# schematic_complete.net
KiCad netlist of a schematic drawn in Altium Designer
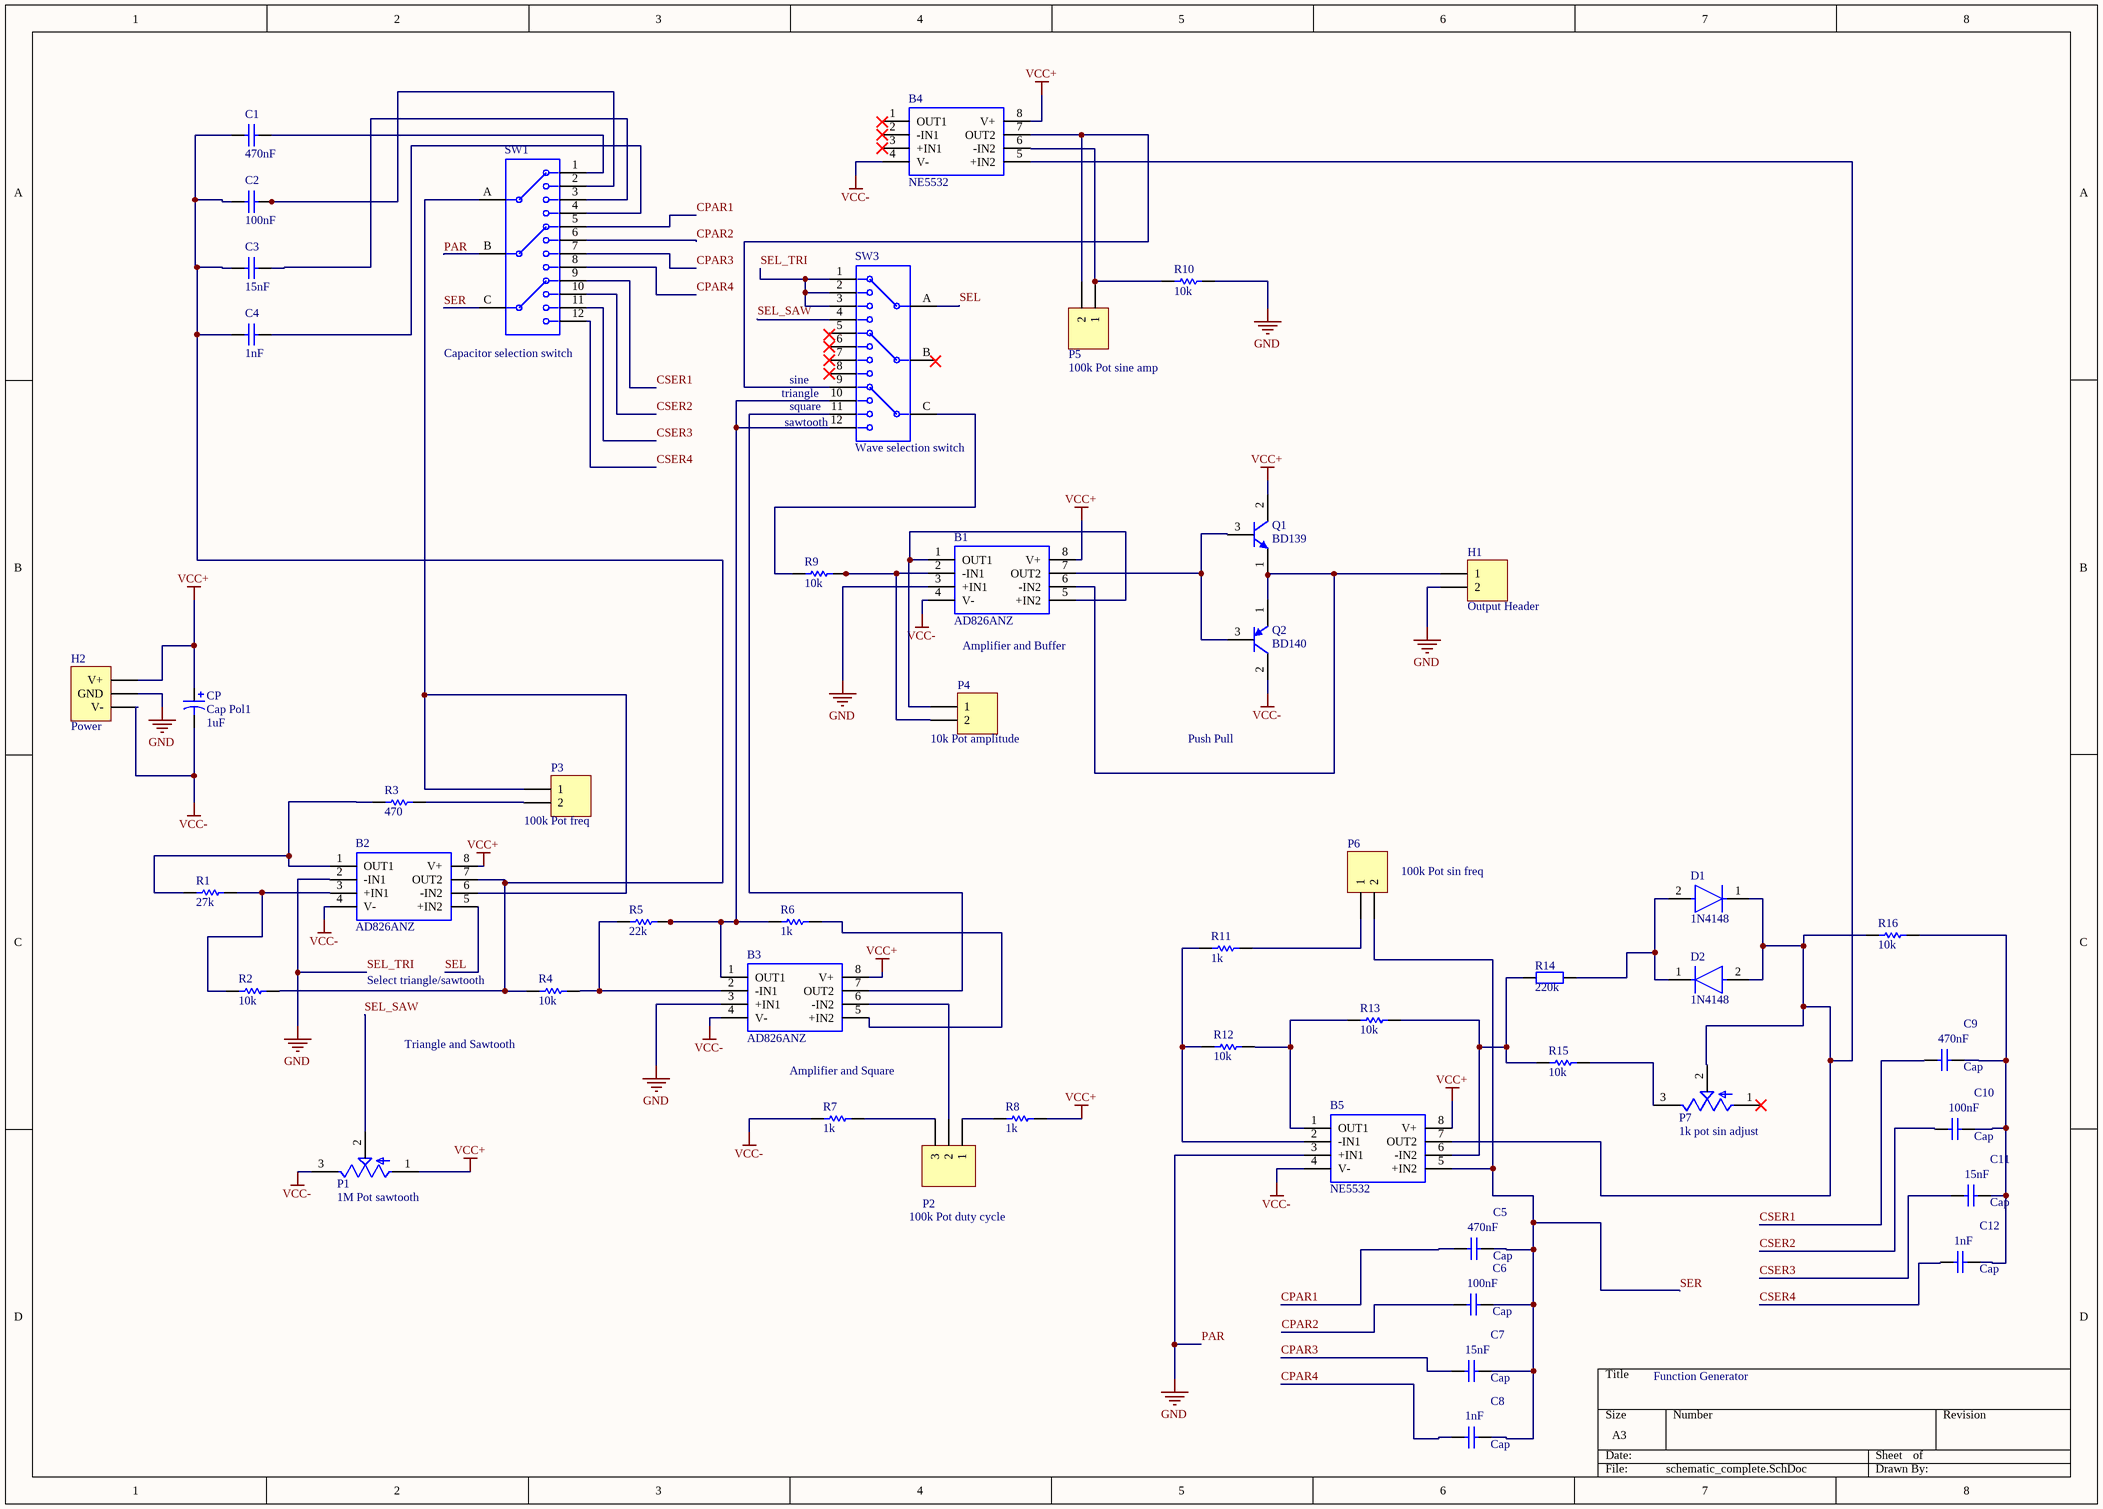
[diagram p0: schematic_complete.SchDoc]

(export (version "E")
  (design (tool "Eeschema 10.0.6"))
  (components
    (comp (ref "B1")
      (value "AD826ANZ")
      (footprint "DIP794W56P254L959H533Q8N")
      (description "AD826ANZ, Dual Operational Amplifier Voltage Feedback 29MHz 9 to 28V, 8-Pin MPDIP")
      (fields (field (name "MOUSER PART NUMBER") "584-AD826ANZ"))
      (libsource (lib "AD826ANZ") (part "AD826ANZ"))
    )
    (comp (ref "B2")
      (value "AD826ANZ")
      (footprint "DIP794W56P254L959H533Q8N")
      (description "AD826ANZ, Dual Operational Amplifier Voltage Feedback 29MHz 9 to 28V, 8-Pin MPDIP")
      (fields (field (name "MOUSER PART NUMBER") "584-AD826ANZ"))
      (libsource (lib "AD826ANZ") (part "AD826ANZ"))
    )
    (comp (ref "B3")
      (value "AD826ANZ")
      (footprint "DIP794W56P254L959H533Q8N:DIP794W56P254L959H533Q8N")
      (description "AD826ANZ, Dual Operational Amplifier Voltage Feedback 29MHz 9 to 28V, 8-Pin MPDIP")
      (fields (field (name "MOUSER PART NUMBER") "584-AD826ANZ"))
      (libsource (lib "AD826ANZ") (part "AD826ANZ"))
    )
    (comp (ref "B4")
      (value "NE5532")
      (footprint "DIP794W56P254L959H533Q8N")
      (description "AD826ANZ, Dual Operational Amplifier Voltage Feedback 29MHz 9 to 28V, 8-Pin MPDIP")
      (fields
        (field (name "MANUFACTURER_PART_NUMBER") "AD826ANZ")
        (field (name "MOUSER PART NUMBER") "584-AD826ANZ")
      )
      (libsource (lib "AD826ANZ") (part "AD826ANZ"))
    )
    (comp (ref "B5")
      (value "NE5532")
      (footprint "DIP794W56P254L959H533Q8N")
      (description "AD826ANZ, Dual Operational Amplifier Voltage Feedback 29MHz 9 to 28V, 8-Pin MPDIP")
      (fields
        (field (name "MANUFACTURER_PART_NUMBER") "AD826ANZ")
        (field (name "MOUSER PART NUMBER") "584-AD826ANZ")
      )
      (libsource (lib "switch") (part "AD826ANZ"))
    )
    (comp (ref "C1")
      (value "470nF")
      (footprint "RAD-0.3")
      (description "Capacitor")
      (fields (field (name "PUBLISHER") "Altium Limited"))
      (libsource (lib "Miscellaneous Devices") (part "Cap"))
    )
    (comp (ref "C2")
      (value "100nF")
      (footprint "RAD-0.3")
      (description "Capacitor")
      (fields (field (name "PUBLISHER") "Altium Limited"))
      (libsource (lib "Miscellaneous Devices") (part "Cap"))
    )
    (comp (ref "C3")
      (value "15nF")
      (footprint "RAD-0.3")
      (description "Capacitor")
      (fields (field (name "PUBLISHER") "Altium Limited"))
      (libsource (lib "Miscellaneous Devices") (part "Cap"))
    )
    (comp (ref "C4")
      (value "1nF")
      (footprint "RAD-0.3")
      (description "Capacitor")
      (fields (field (name "PUBLISHER") "Altium Limited"))
      (libsource (lib "Miscellaneous Devices") (part "Cap"))
    )
    (comp (ref "C5")
      (value "Cap")
      (footprint "RAD-0.3")
      (description "Capacitor")
      (fields (field (name "ALTIUM_VALUE") "470nF") (field (name "PUBLISHER") "Altium Limited"))
      (libsource (lib "Miscellaneous Devices") (part "Cap"))
    )
    (comp (ref "C6")
      (value "Cap")
      (footprint "RAD-0.3")
      (description "Capacitor")
      (fields (field (name "ALTIUM_VALUE") "100nF") (field (name "PUBLISHER") "Altium Limited"))
      (libsource (lib "Miscellaneous Devices") (part "Cap"))
    )
    (comp (ref "C7")
      (value "Cap")
      (footprint "RAD-0.3")
      (description "Capacitor")
      (fields (field (name "ALTIUM_VALUE") "15nF") (field (name "PUBLISHER") "Altium Limited"))
      (libsource (lib "Miscellaneous Devices") (part "Cap"))
    )
    (comp (ref "C8")
      (value "Cap")
      (footprint "RAD-0.3")
      (description "Capacitor")
      (fields (field (name "ALTIUM_VALUE") "1nF") (field (name "PUBLISHER") "Altium Limited"))
      (libsource (lib "Miscellaneous Devices") (part "Cap"))
    )
    (comp (ref "C9")
      (value "Cap")
      (footprint "RAD-0.3")
      (description "Capacitor")
      (fields (field (name "ALTIUM_VALUE") "470nF") (field (name "PUBLISHER") "Altium Limited"))
      (libsource (lib "Miscellaneous Devices") (part "Cap"))
    )
    (comp (ref "C10")
      (value "Cap")
      (footprint "RAD-0.3")
      (description "Capacitor")
      (fields (field (name "ALTIUM_VALUE") "100nF") (field (name "PUBLISHER") "Altium Limited"))
      (libsource (lib "Miscellaneous Devices") (part "Cap"))
    )
    (comp (ref "C11")
      (value "Cap")
      (footprint "RAD-0.3")
      (description "Capacitor")
      (fields (field (name "ALTIUM_VALUE") "15nF") (field (name "PUBLISHER") "Altium Limited"))
      (libsource (lib "Miscellaneous Devices") (part "Cap"))
    )
    (comp (ref "C12")
      (value "Cap")
      (footprint "RAD-0.3")
      (description "Capacitor")
      (fields (field (name "ALTIUM_VALUE") "1nF") (field (name "PUBLISHER") "Altium Limited"))
      (libsource (lib "Miscellaneous Devices") (part "Cap"))
    )
    (comp (ref "CP")
      (value "Cap Pol1")
      (footprint "RB7.6-15")
      (description "Polarized Capacitor (Radial)")
      (fields (field (name "ALTIUM_VALUE") "1uF") (field (name "PUBLISHER") "Altium Limited"))
      (libsource (lib "Miscellaneous Devices") (part "Cap Pol1"))
    )
    (comp (ref "D1")
      (value "1N4148")
      (footprint "FP-017AG-MFG")
      (description "DIODE GEN PURP 100V 200MA DO35")
      (fields (field (name "VOLTAGE") "100V"))
      (libsource (lib "Altium Content Vault") (part "d7152d700b627762746794eb795d46e"))
    )
    (comp (ref "D2")
      (value "1N4148")
      (footprint "FP-017AG-MFG")
      (description "DIODE GEN PURP 100V 200MA DO35")
      (fields (field (name "VOLTAGE") "100V"))
      (libsource (lib "Altium Content Vault") (part "d7152d700b627762746794eb795d46e"))
    )
    (comp (ref "H1")
      (value "Output Header")
      (footprint "HDR1X2")
      (description "Header, 2-Pin")
      (fields (field (name "PUBLISHER") "Altium Limited"))
      (libsource (lib "Miscellaneous Connectors") (part "Header 2"))
    )
    (comp (ref "H2")
      (value "Power")
      (footprint "HDR1X3")
      (description "Header, 3-Pin")
      (fields (field (name "PUBLISHER") "Altium Limited"))
      (libsource (lib "Miscellaneous Connectors") (part "Header 3"))
    )
    (comp (ref "P1")
      (value "1M Pot sawtooth")
      (footprint "TRIM_3362P-1-253LF")
      (description "25 kOhms 0.5W, 1/2W PC Pins Through Hole Trimmer Potentiometer Cermet 1 Turn Top Adjustment")
      (fields (field (name "MF") "Bourns") (field (name "MP") "3362P-1-253LF"))
      (libsource (lib "3362P-1-253LF") (part "3362P-1-253LF"))
    )
    (comp (ref "P2")
      (value "100k Pot duty cycle")
      (footprint "HDR1X3")
      (description "Header, 3-Pin")
      (fields (field (name "PUBLISHER") "Altium Limited"))
      (libsource (lib "Miscellaneous Connectors") (part "Header 3"))
    )
    (comp (ref "P3")
      (value "100k Pot freq")
      (footprint "HDR1X2")
      (description "Header, 2-Pin")
      (fields (field (name "PUBLISHER") "Altium Limited"))
      (libsource (lib "Miscellaneous Connectors") (part "Header 2"))
    )
    (comp (ref "P4")
      (value "10k Pot amplitude")
      (footprint "HDR1X2")
      (description "Header, 2-Pin")
      (fields (field (name "PUBLISHER") "Altium Limited"))
      (libsource (lib "Miscellaneous Connectors") (part "Header 2"))
    )
    (comp (ref "P5")
      (value "100k Pot sine amp")
      (footprint "HDR1X2")
      (description "Header, 2-Pin")
      (fields (field (name "PUBLISHER") "Altium Limited"))
      (libsource (lib "") (part "Header 2_2"))
    )
    (comp (ref "P6")
      (value "100k Pot sin freq")
      (footprint "HDR1X2")
      (description "Header, 2-Pin")
      (fields (field (name "PUBLISHER") "Altium Limited"))
      (libsource (lib "") (part "Header 2_1"))
    )
    (comp (ref "P7")
      (value "1k pot sin adjust")
      (footprint "TRIM_3362P-1-253LF")
      (description "25 kOhms 0.5W, 1/2W PC Pins Through Hole Trimmer Potentiometer Cermet 1 Turn Top Adjustment")
      (fields (field (name "MF") "Bourns") (field (name "MP") "3362P-1-253LF"))
      (libsource (lib "3362P-1-253LF") (part "3362P-1-253LF"))
    )
    (comp (ref "Q1")
      (value "BD139")
      (footprint "ONSC-TO-225-3-77-09")
      (description "Plastic Medium-Power Silicon NPN Transistor, 3-Pin TO-225, Bulk Box")
      (fields (field (name "MANUFACTURER") "On Semiconductor"))
      (libsource (lib "Altium Content Vault") (part "ONSC-NPN-E1C2B3-3"))
    )
    (comp (ref "Q2")
      (value "BD140")
      (footprint "ONSC-TO-225-3-77-09")
      (description "Plastic Medium-Power Silicon PNP Transistor, 3-Pin TO-225, Bulk Box")
      (fields (field (name "MANUFACTURER") "On Semiconductor"))
      (libsource (lib "Altium Content Vault") (part "ONSC-PNP-E1C2B3-3"))
    )
    (comp (ref "R1")
      (value "27k")
      (footprint "AXIAL-0.3")
      (description "Resistor")
      (fields (field (name "PUBLISHER") "Altium Limited"))
      (libsource (lib "Miscellaneous Devices") (part "Res1"))
    )
    (comp (ref "R2")
      (value "10k")
      (footprint "AXIAL-0.3")
      (description "Resistor")
      (fields (field (name "PUBLISHER") "Altium Limited"))
      (libsource (lib "Miscellaneous Devices") (part "Res1"))
    )
    (comp (ref "R3")
      (value "470")
      (footprint "AXIAL-0.3")
      (description "Resistor")
      (fields (field (name "PUBLISHER") "Altium Limited"))
      (libsource (lib "Miscellaneous Devices") (part "Res1"))
    )
    (comp (ref "R4")
      (value "10k")
      (footprint "AXIAL-0.3")
      (description "Resistor")
      (fields (field (name "PUBLISHER") "Altium Limited"))
      (libsource (lib "Miscellaneous Devices") (part "Res1"))
    )
    (comp (ref "R5")
      (value "22k")
      (footprint "AXIAL-0.3")
      (description "Resistor")
      (fields (field (name "PUBLISHER") "Altium Limited"))
      (libsource (lib "Miscellaneous Devices") (part "Res1"))
    )
    (comp (ref "R6")
      (value "1k")
      (footprint "AXIAL-0.3")
      (description "Resistor")
      (fields (field (name "PUBLISHER") "Altium Limited"))
      (libsource (lib "Miscellaneous Devices") (part "Res1"))
    )
    (comp (ref "R7")
      (value "1k")
      (footprint "AXIAL-0.3")
      (description "Resistor")
      (fields (field (name "PUBLISHER") "Altium Limited"))
      (libsource (lib "Miscellaneous Devices") (part "Res1"))
    )
    (comp (ref "R8")
      (value "1k")
      (footprint "AXIAL-0.3")
      (description "Resistor")
      (fields (field (name "PUBLISHER") "Altium Limited"))
      (libsource (lib "Miscellaneous Devices") (part "Res1"))
    )
    (comp (ref "R9")
      (value "10k")
      (footprint "AXIAL-0.3")
      (description "Resistor")
      (fields (field (name "PUBLISHER") "Altium Limited"))
      (libsource (lib "Miscellaneous Devices") (part "Res1"))
    )
    (comp (ref "R10")
      (value "10k")
      (footprint "AXIAL-0.3")
      (description "Resistor")
      (fields (field (name "PUBLISHER") "Altium Limited"))
      (libsource (lib "Miscellaneous Devices") (part "Res1"))
    )
    (comp (ref "R11")
      (value "1k")
      (footprint "AXIAL-0.3")
      (description "Resistor")
      (fields (field (name "PUBLISHER") "Altium Limited"))
      (libsource (lib "Miscellaneous Devices") (part "Res1"))
    )
    (comp (ref "R12")
      (value "10k")
      (footprint "AXIAL-0.3")
      (description "Resistor")
      (fields (field (name "PUBLISHER") "Altium Limited"))
      (libsource (lib "Miscellaneous Devices") (part "Res1"))
    )
    (comp (ref "R13")
      (value "10k")
      (footprint "AXIAL-0.3")
      (description "Resistor")
      (fields (field (name "PUBLISHER") "Altium Limited"))
      (libsource (lib "Miscellaneous Devices") (part "Res1"))
    )
    (comp (ref "R14")
      (value "220k")
      (footprint "AXIAL-0.4")
      (description "Resistor")
      (fields (field (name "PUBLISHER") "Altium Limited"))
      (libsource (lib "Miscellaneous Devices") (part "Res2"))
    )
    (comp (ref "R15")
      (value "10k")
      (footprint "AXIAL-0.3")
      (description "Resistor")
      (fields (field (name "PUBLISHER") "Altium Limited"))
      (libsource (lib "Miscellaneous Devices") (part "Res1"))
    )
    (comp (ref "R16")
      (value "10k")
      (footprint "AXIAL-0.3")
      (description "Resistor")
      (fields (field (name "PUBLISHER") "Altium Limited"))
      (libsource (lib "Miscellaneous Devices") (part "Res1"))
    )
    (comp (ref "SW1")
      (value "Capacitor selection switch")
      (footprint "SW_A30403RNCQ")
      (description "Rotary Switch 4 Position 3P4T 2.5A (AC), 350mA (DC) 125VAC Panel Mount, Through Hole")
      (fields (field (name "MP") "A30403RNCQ") (field (name "MF") "C&K"))
      (libsource (lib "A30403RNCQ") (part "A30403RNCQ"))
    )
    (comp (ref "SW3")
      (value "Wave selection switch")
      (footprint "SW_A30403RNCQ")
      (description "Rotary Switch 4 Position 3P4T 2.5A (AC), 350mA (DC) 125VAC Panel Mount, Through Hole")
      (fields (field (name "MP") "A30403RNCQ") (field (name "MF") "C&K"))
      (libsource (lib "A30403RNCQ") (part "A30403RNCQ"))
    )
  )
  (nets
    (net (code "1") (name "/CPAR1") (class "Default")
      (node (ref "C5") (pin "1") (pinfunction "1_1") (pintype "passive"))
      (node (ref "SW1") (pin "5") (pinfunction "5_5") (pintype "passive"))
    )
    (net (code "2") (name "/CPAR2") (class "Default")
      (node (ref "C6") (pin "1") (pinfunction "1_1") (pintype "passive"))
      (node (ref "SW1") (pin "6") (pinfunction "6_6") (pintype "passive"))
    )
    (net (code "3") (name "/CPAR3") (class "Default")
      (node (ref "C7") (pin "1") (pinfunction "1_1") (pintype "passive"))
      (node (ref "SW1") (pin "7") (pinfunction "7_7") (pintype "passive"))
    )
    (net (code "4") (name "/CPAR4") (class "Default")
      (node (ref "C8") (pin "1") (pinfunction "1_1") (pintype "passive"))
      (node (ref "SW1") (pin "8") (pinfunction "8_8") (pintype "passive"))
    )
    (net (code "5") (name "/CSER1") (class "Default")
      (node (ref "C9") (pin "1") (pinfunction "1_1") (pintype "passive"))
      (node (ref "SW1") (pin "9") (pinfunction "9_9") (pintype "passive"))
    )
    (net (code "6") (name "/CSER2") (class "Default")
      (node (ref "C10") (pin "1") (pinfunction "1_1") (pintype "passive"))
      (node (ref "SW1") (pin "10") (pinfunction "10_10") (pintype "passive"))
    )
    (net (code "7") (name "/CSER3") (class "Default")
      (node (ref "C11") (pin "1") (pinfunction "1_1") (pintype "passive"))
      (node (ref "SW1") (pin "11") (pinfunction "11_11") (pintype "passive"))
    )
    (net (code "8") (name "/CSER4") (class "Default")
      (node (ref "C12") (pin "1") (pinfunction "1_1") (pintype "passive"))
      (node (ref "SW1") (pin "12") (pinfunction "12_12") (pintype "passive"))
    )
    (net (code "9") (name "/SEL") (class "Default")
      (node (ref "B2") (pin "5") (pinfunction "+IN2_5") (pintype "passive"))
      (node (ref "SW3") (pin "A") (pinfunction "A_A") (pintype "passive"))
    )
    (net (code "10") (name "/SEL_SAW") (class "Default")
      (node (ref "P1") (pin "2") (pinfunction "WIPER_2") (pintype "passive"))
      (node (ref "SW3") (pin "4") (pinfunction "4_4") (pintype "passive"))
    )
    (net (code "11") (name "/SER") (class "Default")
      (node (ref "B5") (pin "5") (pinfunction "+IN2_5") (pintype "passive"))
      (node (ref "C5") (pin "2") (pinfunction "2_2") (pintype "passive"))
      (node (ref "C6") (pin "2") (pinfunction "2_2") (pintype "passive"))
      (node (ref "C7") (pin "2") (pinfunction "2_2") (pintype "passive"))
      (node (ref "C8") (pin "2") (pinfunction "2_2") (pintype "passive"))
      (node (ref "P6") (pin "2") (pinfunction "2_2") (pintype "passive"))
      (node (ref "SW1") (pin "C") (pinfunction "C_C") (pintype "passive"))
    )
    (net (code "12") (name "GND") (class "Default")
      (node (ref "B1") (pin "3") (pinfunction "+IN1_3") (pintype "passive"))
      (node (ref "B2") (pin "2") (pinfunction "-IN1_2") (pintype "passive"))
      (node (ref "B3") (pin "3") (pinfunction "+IN1_3") (pintype "passive"))
      (node (ref "B5") (pin "3") (pinfunction "+IN1_3") (pintype "passive"))
      (node (ref "H1") (pin "2") (pinfunction "2_2") (pintype "passive"))
      (node (ref "H2") (pin "2") (pinfunction "GND_2") (pintype "passive"))
      (node (ref "R10") (pin "2") (pinfunction "2_2") (pintype "passive"))
      (node (ref "SW1") (pin "B") (pinfunction "B_B") (pintype "passive"))
      (node (ref "SW3") (pin "1") (pinfunction "1_1") (pintype "passive"))
      (node (ref "SW3") (pin "2") (pinfunction "2_2") (pintype "passive"))
      (node (ref "SW3") (pin "3") (pinfunction "3_3") (pintype "passive"))
    )
    (net (code "13") (name "Net-(B1-+IN2)") (class "Default")
      (node (ref "B1") (pin "1") (pinfunction "OUT1_1") (pintype "passive"))
      (node (ref "B1") (pin "5") (pinfunction "+IN2_5") (pintype "passive"))
      (node (ref "P4") (pin "1") (pinfunction "1_1") (pintype "passive"))
    )
    (net (code "14") (name "Net-(B1--IN1)") (class "Default")
      (node (ref "B1") (pin "2") (pinfunction "-IN1_2") (pintype "passive"))
      (node (ref "P4") (pin "2") (pinfunction "2_2") (pintype "passive"))
      (node (ref "R9") (pin "2") (pinfunction "2_2") (pintype "passive"))
    )
    (net (code "15") (name "Net-(B1--IN2)") (class "Default")
      (node (ref "B1") (pin "6") (pinfunction "-IN2_6") (pintype "passive"))
      (node (ref "H1") (pin "1") (pinfunction "1_1") (pintype "passive"))
      (node (ref "Q1") (pin "1") (pinfunction "E_1") (pintype "passive"))
      (node (ref "Q2") (pin "1") (pinfunction "E_1") (pintype "passive"))
    )
    (net (code "16") (name "Net-(B1-OUT2)") (class "Default")
      (node (ref "B1") (pin "7") (pinfunction "OUT2_7") (pintype "passive"))
      (node (ref "Q1") (pin "3") (pinfunction "B_3") (pintype "passive"))
      (node (ref "Q2") (pin "3") (pinfunction "B_3") (pintype "passive"))
    )
    (net (code "17") (name "Net-(B2-+IN1)") (class "Default")
      (node (ref "B2") (pin "3") (pinfunction "+IN1_3") (pintype "passive"))
      (node (ref "R1") (pin "2") (pinfunction "2_2") (pintype "passive"))
      (node (ref "R2") (pin "1") (pinfunction "1_1") (pintype "passive"))
    )
    (net (code "18") (name "Net-(B2--IN2)") (class "Default")
      (node (ref "B2") (pin "6") (pinfunction "-IN2_6") (pintype "passive"))
      (node (ref "P3") (pin "1") (pinfunction "1_1") (pintype "passive"))
      (node (ref "SW1") (pin "A") (pinfunction "A_A") (pintype "passive"))
    )
    (net (code "19") (name "Net-(B2-OUT1)") (class "Default")
      (node (ref "B2") (pin "1") (pinfunction "OUT1_1") (pintype "passive"))
      (node (ref "R1") (pin "1") (pinfunction "1_1") (pintype "passive"))
      (node (ref "R3") (pin "1") (pinfunction "1_1") (pintype "passive"))
    )
    (net (code "20") (name "Net-(B2-OUT2)") (class "Default")
      (node (ref "B2") (pin "7") (pinfunction "OUT2_7") (pintype "passive"))
      (node (ref "C1") (pin "1") (pinfunction "1_1") (pintype "passive"))
      (node (ref "C2") (pin "1") (pinfunction "1_1") (pintype "passive"))
      (node (ref "C3") (pin "1") (pinfunction "1_1") (pintype "passive"))
      (node (ref "C4") (pin "1") (pinfunction "1_1") (pintype "passive"))
      (node (ref "R2") (pin "2") (pinfunction "2_2") (pintype "passive"))
      (node (ref "R4") (pin "1") (pinfunction "1_1") (pintype "passive"))
    )
    (net (code "21") (name "Net-(B3-+IN2)") (class "Default")
      (node (ref "B3") (pin "5") (pinfunction "+IN2_5") (pintype "passive"))
      (node (ref "R6") (pin "2") (pinfunction "2_2") (pintype "passive"))
    )
    (net (code "22") (name "Net-(B3--IN1)") (class "Default")
      (node (ref "B3") (pin "2") (pinfunction "-IN1_2") (pintype "passive"))
      (node (ref "R4") (pin "2") (pinfunction "2_2") (pintype "passive"))
      (node (ref "R5") (pin "1") (pinfunction "1_1") (pintype "passive"))
    )
    (net (code "23") (name "Net-(B3--IN2)") (class "Default")
      (node (ref "B3") (pin "6") (pinfunction "-IN2_6") (pintype "passive"))
      (node (ref "P2") (pin "2") (pinfunction "GND_2") (pintype "passive"))
    )
    (net (code "24") (name "Net-(B3-OUT1)") (class "Default")
      (node (ref "B3") (pin "1") (pinfunction "OUT1_1") (pintype "passive"))
      (node (ref "R5") (pin "2") (pinfunction "2_2") (pintype "passive"))
      (node (ref "R6") (pin "1") (pinfunction "1_1") (pintype "passive"))
      (node (ref "SW3") (pin "10") (pinfunction "10_10") (pintype "passive"))
      (node (ref "SW3") (pin "12") (pinfunction "12_12") (pintype "passive"))
    )
    (net (code "25") (name "Net-(B3-OUT2)") (class "Default")
      (node (ref "B3") (pin "7") (pinfunction "OUT2_7") (pintype "passive"))
      (node (ref "SW3") (pin "11") (pinfunction "11_11") (pintype "passive"))
    )
    (net (code "26") (name "Net-(B4-+IN2)") (class "Default")
      (node (ref "B4") (pin "5") (pinfunction "+IN2_5") (pintype "passive"))
      (node (ref "B5") (pin "7") (pinfunction "OUT2_7") (pintype "passive"))
      (node (ref "D1") (pin "1") (pinfunction "C_1") (pintype "passive"))
      (node (ref "D2") (pin "2") (pinfunction "A_2") (pintype "passive"))
      (node (ref "P7") (pin "2") (pinfunction "WIPER_2") (pintype "passive"))
      (node (ref "R16") (pin "1") (pinfunction "1_1") (pintype "passive"))
    )
    (net (code "27") (name "Net-(B4--IN2)") (class "Default")
      (node (ref "B4") (pin "6") (pinfunction "-IN2_6") (pintype "passive"))
      (node (ref "P5") (pin "1") (pinfunction "1_1") (pintype "passive"))
      (node (ref "R10") (pin "1") (pinfunction "1_1") (pintype "passive"))
    )
    (net (code "28") (name "Net-(B4-OUT2)") (class "Default")
      (node (ref "B4") (pin "7") (pinfunction "OUT2_7") (pintype "passive"))
      (node (ref "P5") (pin "2") (pinfunction "2_2") (pintype "passive"))
      (node (ref "SW3") (pin "9") (pinfunction "9_9") (pintype "passive"))
    )
    (net (code "29") (name "Net-(B5--IN1)") (class "Default")
      (node (ref "B5") (pin "2") (pinfunction "-IN1_2") (pintype "passive"))
      (node (ref "R11") (pin "1") (pinfunction "1_1") (pintype "passive"))
      (node (ref "R12") (pin "1") (pinfunction "1_1") (pintype "passive"))
    )
    (net (code "30") (name "Net-(B5--IN2)") (class "Default")
      (node (ref "B5") (pin "6") (pinfunction "-IN2_6") (pintype "passive"))
      (node (ref "R13") (pin "2") (pinfunction "2_2") (pintype "passive"))
      (node (ref "R14") (pin "1") (pinfunction "1_1") (pintype "passive"))
      (node (ref "R15") (pin "1") (pinfunction "1_1") (pintype "passive"))
    )
    (net (code "31") (name "Net-(B5-OUT1)") (class "Default")
      (node (ref "B5") (pin "1") (pinfunction "OUT1_1") (pintype "passive"))
      (node (ref "R12") (pin "2") (pinfunction "2_2") (pintype "passive"))
      (node (ref "R13") (pin "1") (pinfunction "1_1") (pintype "passive"))
    )
    (net (code "32") (name "Net-(C1-Pad2)") (class "Default")
      (node (ref "C1") (pin "2") (pinfunction "2_2") (pintype "passive"))
      (node (ref "SW1") (pin "1") (pinfunction "1_1") (pintype "passive"))
    )
    (net (code "33") (name "Net-(C2-Pad2)") (class "Default")
      (node (ref "C2") (pin "2") (pinfunction "2_2") (pintype "passive"))
      (node (ref "SW1") (pin "2") (pinfunction "2_2") (pintype "passive"))
    )
    (net (code "34") (name "Net-(C3-Pad2)") (class "Default")
      (node (ref "C3") (pin "2") (pinfunction "2_2") (pintype "passive"))
      (node (ref "SW1") (pin "3") (pinfunction "3_3") (pintype "passive"))
    )
    (net (code "35") (name "Net-(C4-Pad2)") (class "Default")
      (node (ref "C4") (pin "2") (pinfunction "2_2") (pintype "passive"))
      (node (ref "SW1") (pin "4") (pinfunction "4_4") (pintype "passive"))
    )
    (net (code "36") (name "Net-(C10-Pad2)") (class "Default")
      (node (ref "C10") (pin "2") (pinfunction "2_2") (pintype "passive"))
      (node (ref "C11") (pin "2") (pinfunction "2_2") (pintype "passive"))
      (node (ref "C12") (pin "2") (pinfunction "2_2") (pintype "passive"))
      (node (ref "C9") (pin "2") (pinfunction "2_2") (pintype "passive"))
      (node (ref "R16") (pin "2") (pinfunction "2_2") (pintype "passive"))
    )
    (net (code "37") (name "Net-(D1-A)") (class "Default")
      (node (ref "D1") (pin "2") (pinfunction "A_2") (pintype "passive"))
      (node (ref "D2") (pin "1") (pinfunction "C_1") (pintype "passive"))
      (node (ref "R14") (pin "2") (pinfunction "2_2") (pintype "passive"))
    )
    (net (code "38") (name "Net-(P2-V+)") (class "Default")
      (node (ref "P2") (pin "1") (pinfunction "V+_1") (pintype "passive"))
      (node (ref "R8") (pin "1") (pinfunction "1_1") (pintype "passive"))
    )
    (net (code "39") (name "Net-(P2-V-)") (class "Default")
      (node (ref "P2") (pin "3") (pinfunction "V-_3") (pintype "passive"))
      (node (ref "R7") (pin "2") (pinfunction "2_2") (pintype "passive"))
    )
    (net (code "40") (name "Net-(P3-Pad2)") (class "Default")
      (node (ref "P3") (pin "2") (pinfunction "2_2") (pintype "passive"))
      (node (ref "R3") (pin "2") (pinfunction "2_2") (pintype "passive"))
    )
    (net (code "41") (name "Net-(P6-Pad1)") (class "Default")
      (node (ref "P6") (pin "1") (pinfunction "1_1") (pintype "passive"))
      (node (ref "R11") (pin "2") (pinfunction "2_2") (pintype "passive"))
    )
    (net (code "42") (name "Net-(P7-CW)") (class "Default")
      (node (ref "P7") (pin "3") (pinfunction "CW_3") (pintype "passive"))
      (node (ref "R15") (pin "2") (pinfunction "2_2") (pintype "passive"))
    )
    (net (code "43") (name "Net-(R9-Pad1)") (class "Default")
      (node (ref "R9") (pin "1") (pinfunction "1_1") (pintype "passive"))
      (node (ref "SW3") (pin "C") (pinfunction "C_C") (pintype "passive"))
    )
    (net (code "44") (name "VCC+") (class "Default")
      (node (ref "B1") (pin "8") (pinfunction "V+_8") (pintype "passive"))
      (node (ref "B2") (pin "8") (pinfunction "V+_8") (pintype "passive"))
      (node (ref "B3") (pin "8") (pinfunction "V+_8") (pintype "passive"))
      (node (ref "B4") (pin "8") (pinfunction "V+_8") (pintype "passive"))
      (node (ref "B5") (pin "8") (pinfunction "V+_8") (pintype "passive"))
      (node (ref "CP") (pin "1") (pinfunction "1_1") (pintype "passive"))
      (node (ref "H2") (pin "1") (pinfunction "V+_1") (pintype "passive"))
      (node (ref "P1") (pin "1") (pinfunction "CCW_1") (pintype "passive"))
      (node (ref "Q1") (pin "2") (pinfunction "C_2") (pintype "passive"))
      (node (ref "R8") (pin "2") (pinfunction "2_2") (pintype "passive"))
    )
    (net (code "45") (name "VCC-") (class "Default")
      (node (ref "B1") (pin "4") (pinfunction "V-_4") (pintype "passive"))
      (node (ref "B2") (pin "4") (pinfunction "V-_4") (pintype "passive"))
      (node (ref "B3") (pin "4") (pinfunction "V-_4") (pintype "passive"))
      (node (ref "B4") (pin "4") (pinfunction "V-_4") (pintype "passive"))
      (node (ref "B5") (pin "4") (pinfunction "V-_4") (pintype "passive"))
      (node (ref "CP") (pin "2") (pinfunction "2_2") (pintype "passive"))
      (node (ref "H2") (pin "3") (pinfunction "V-_3") (pintype "passive"))
      (node (ref "P1") (pin "3") (pinfunction "CW_3") (pintype "passive"))
      (node (ref "Q2") (pin "2") (pinfunction "C_2") (pintype "passive"))
      (node (ref "R7") (pin "1") (pinfunction "1_1") (pintype "passive"))
    )
    (net (code "46") (name "unconnected-(B4-+IN1-Pad3)") (class "Default")
      (node (ref "B4") (pin "3") (pinfunction "+IN1_3") (pintype "passive+no_connect"))
    )
    (net (code "47") (name "unconnected-(B4--IN1-Pad2)") (class "Default")
      (node (ref "B4") (pin "2") (pinfunction "-IN1_2") (pintype "passive+no_connect"))
    )
    (net (code "48") (name "unconnected-(B4-OUT1-Pad1)") (class "Default")
      (node (ref "B4") (pin "1") (pinfunction "OUT1_1") (pintype "passive"))
    )
    (net (code "49") (name "unconnected-(P7-CCW-Pad1)") (class "Default")
      (node (ref "P7") (pin "1") (pinfunction "CCW_1") (pintype "passive+no_connect"))
    )
    (net (code "50") (name "unconnected-(SW3-Pad5)") (class "Default")
      (node (ref "SW3") (pin "5") (pinfunction "5_5") (pintype "passive"))
    )
    (net (code "51") (name "unconnected-(SW3-Pad6)") (class "Default")
      (node (ref "SW3") (pin "6") (pinfunction "6_6") (pintype "passive+no_connect"))
    )
    (net (code "52") (name "unconnected-(SW3-Pad7)") (class "Default")
      (node (ref "SW3") (pin "7") (pinfunction "7_7") (pintype "passive+no_connect"))
    )
    (net (code "53") (name "unconnected-(SW3-Pad8)") (class "Default")
      (node (ref "SW3") (pin "8") (pinfunction "8_8") (pintype "passive+no_connect"))
    )
    (net (code "54") (name "unconnected-(SW3-PadB)") (class "Default")
      (node (ref "SW3") (pin "B") (pinfunction "B_B") (pintype "passive"))
    )
  )
)
